# FPGA.net
KiCad netlist of a schematic drawn in Altium Designer
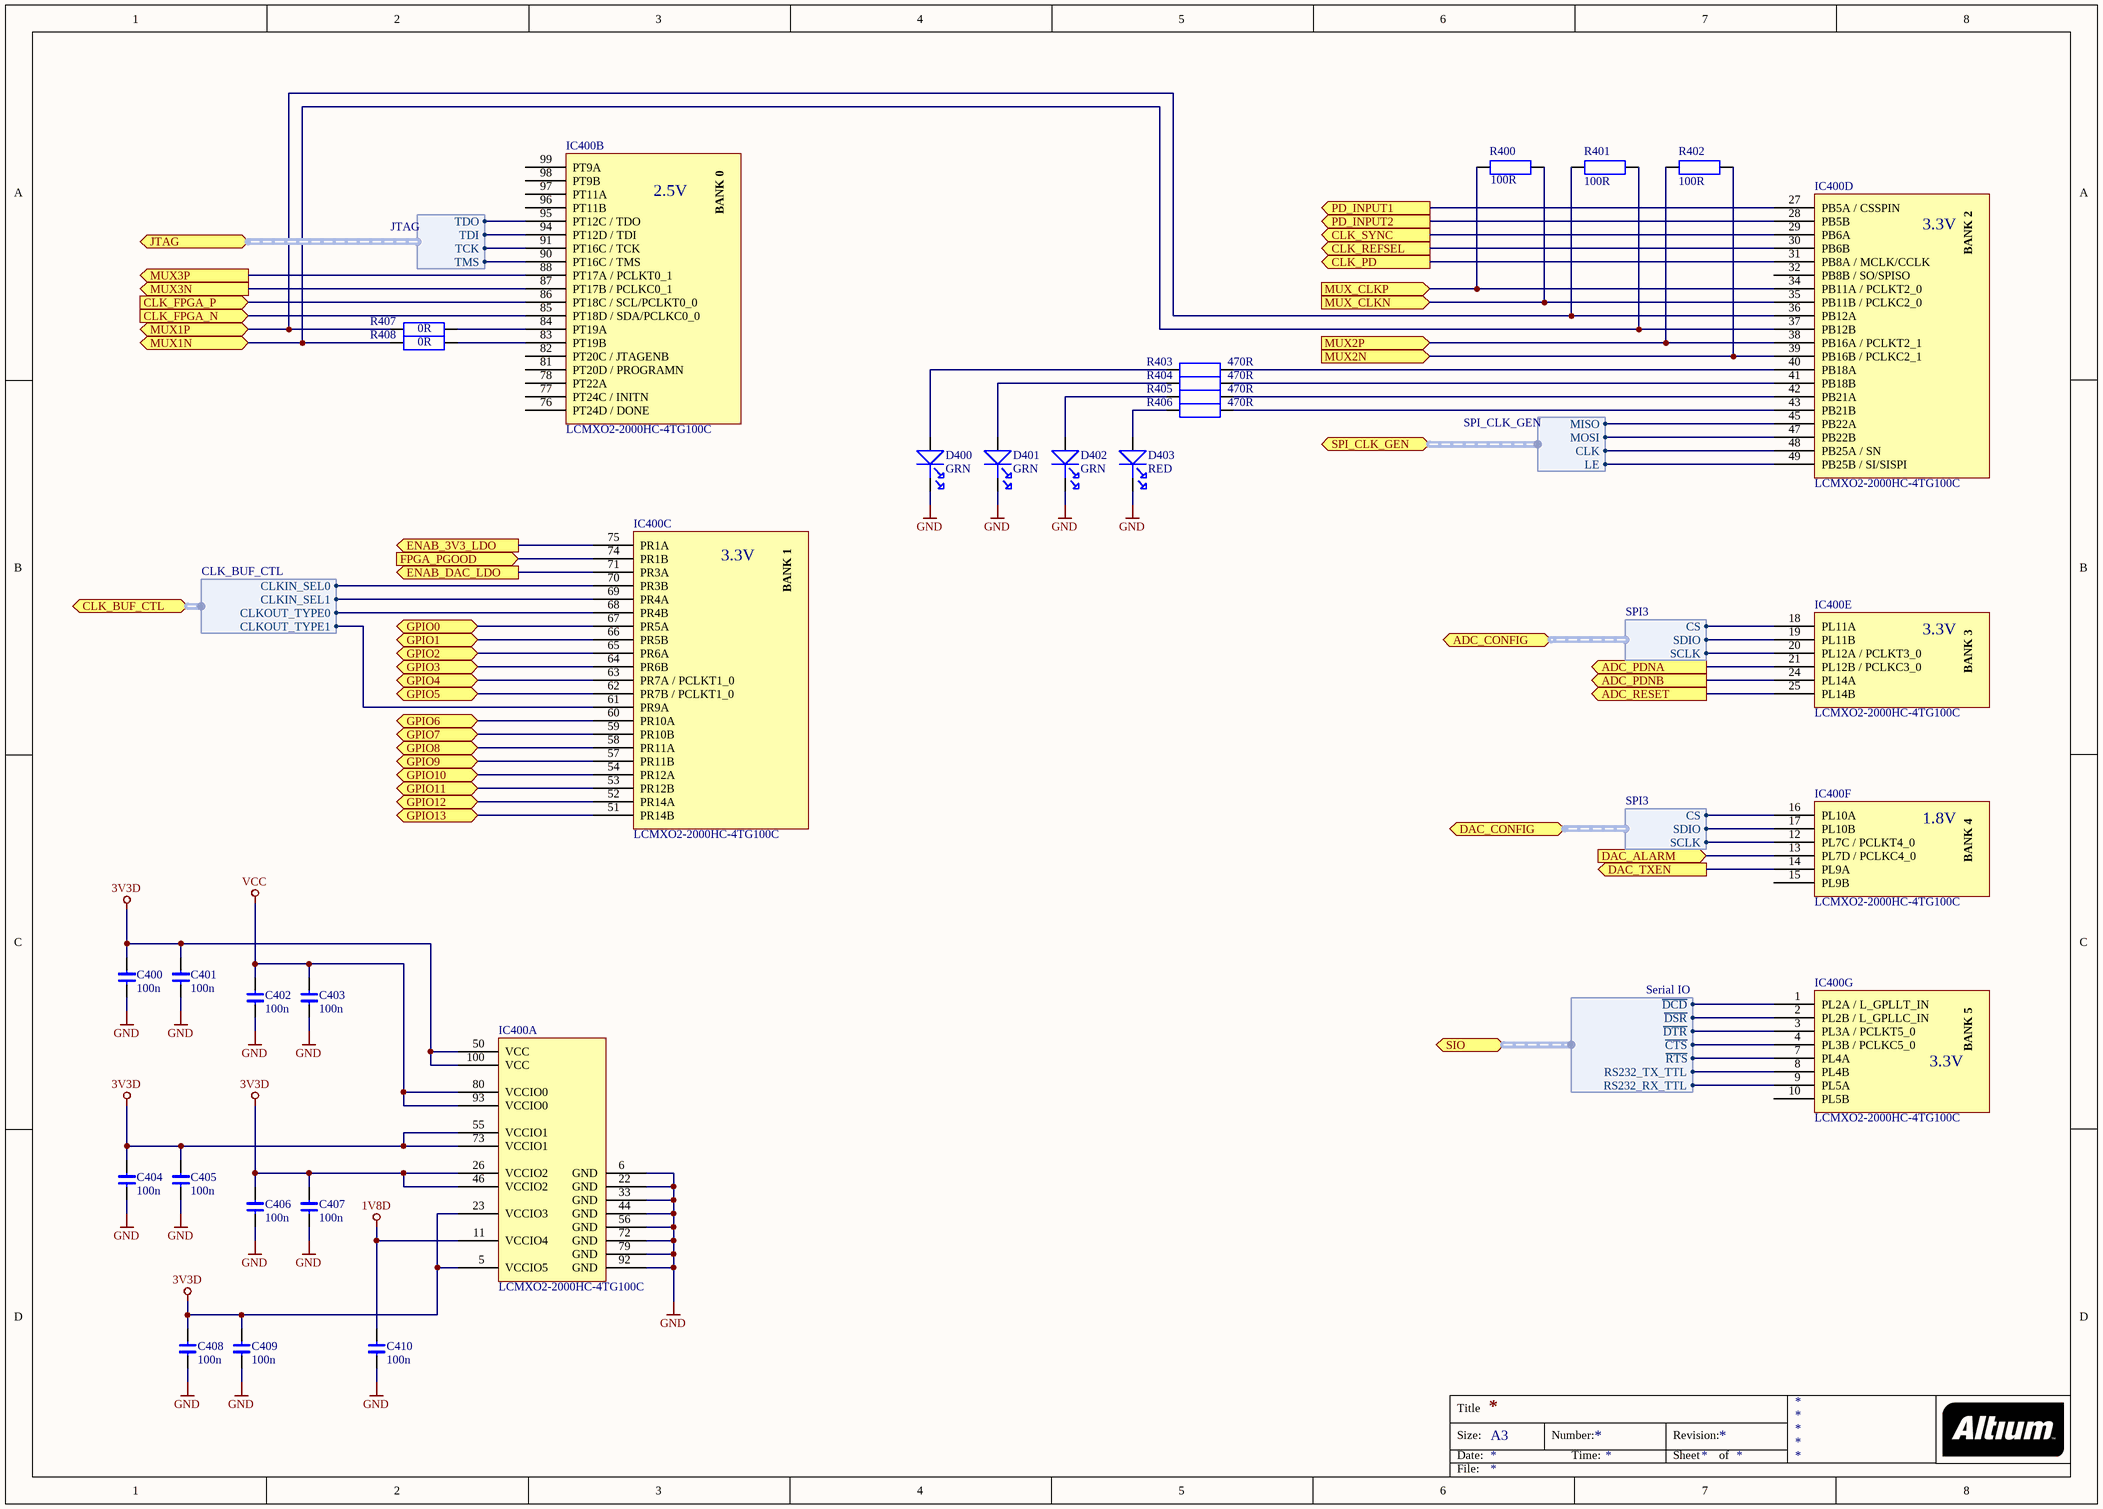
[diagram p0: FPGA.SchDoc]

(export (version "E")
  (design (tool "Eeschema 10.0.6"))
  (components
    (comp (ref "C400")
      (value "100n")
      (footprint "0603 SMALL OUTLINE")
      (description "C")
      (libsource (lib "RCL") (part "C"))
    )
    (comp (ref "C401")
      (value "100n")
      (footprint "0603 SMALL OUTLINE")
      (description "C")
      (libsource (lib "RCL") (part "C"))
    )
    (comp (ref "C402")
      (value "100n")
      (footprint "0603 SMALL OUTLINE")
      (description "C")
      (libsource (lib "RCL") (part "C"))
    )
    (comp (ref "C403")
      (value "100n")
      (footprint "0603 SMALL OUTLINE")
      (description "C")
      (libsource (lib "RCL") (part "C"))
    )
    (comp (ref "C404")
      (value "100n")
      (footprint "0603 SMALL OUTLINE")
      (description "C")
      (libsource (lib "RCL") (part "C"))
    )
    (comp (ref "C405")
      (value "100n")
      (footprint "0603 SMALL OUTLINE")
      (description "C")
      (libsource (lib "RCL") (part "C"))
    )
    (comp (ref "C406")
      (value "100n")
      (footprint "0603 SMALL OUTLINE")
      (description "C")
      (libsource (lib "RCL") (part "C"))
    )
    (comp (ref "C407")
      (value "100n")
      (footprint "0603 SMALL OUTLINE")
      (description "C")
      (libsource (lib "RCL") (part "C"))
    )
    (comp (ref "C408")
      (value "100n")
      (footprint "0603 SMALL OUTLINE")
      (description "C")
      (libsource (lib "RCL") (part "C"))
    )
    (comp (ref "C409")
      (value "100n")
      (footprint "0603 SMALL OUTLINE")
      (description "C")
      (libsource (lib "RCL") (part "C"))
    )
    (comp (ref "C410")
      (value "100n")
      (footprint "0603 SMALL OUTLINE")
      (description "C")
      (libsource (lib "RCL") (part "C"))
    )
    (comp (ref "D400")
      (value "GRN")
      (footprint "LED SMD 0603")
      (description "WURTH 150060VS75000")
      (libsource (lib "OPTO1") (part "LED SMD"))
    )
    (comp (ref "D401")
      (value "GRN")
      (footprint "LED SMD 0603")
      (description "WURTH 150060VS75000")
      (libsource (lib "OPTO1") (part "LED SMD"))
    )
    (comp (ref "D402")
      (value "GRN")
      (footprint "LED SMD 0603")
      (description "WURTH 150060VS75000")
      (libsource (lib "OPTO1") (part "LED SMD"))
    )
    (comp (ref "D403")
      (value "RED")
      (footprint "LED SMD 0603")
      (description "WURTH 150060SS75000")
      (libsource (lib "OPTO1") (part "LED SMD"))
    )
    (comp (ref "IC400")
      (value "LCMXO2-2000HC-4TG100C")
      (footprint "TQFP100")
      (description "Lattice MachXO2")
      (libsource (lib "Private") (part "LCMXO2-2000HC-4TG100C"))
    )
    (comp (ref "R400") (value "100R") (footprint "0402") (description "R") (libsource (lib "RCL") (part "R")))
    (comp (ref "R401") (value "100R") (footprint "0402") (description "R") (libsource (lib "RCL") (part "R")))
    (comp (ref "R402") (value "100R") (footprint "0402") (description "R") (libsource (lib "RCL") (part "R")))
    (comp (ref "R403")
      (value "470R")
      (footprint "0603 SMALL OUTLINE")
      (description "R")
      (libsource (lib "RCL") (part "R"))
    )
    (comp (ref "R404")
      (value "470R")
      (footprint "0603 SMALL OUTLINE")
      (description "R")
      (libsource (lib "RCL") (part "R"))
    )
    (comp (ref "R405")
      (value "470R")
      (footprint "0603 SMALL OUTLINE")
      (description "R")
      (libsource (lib "RCL") (part "R"))
    )
    (comp (ref "R406")
      (value "470R")
      (footprint "0603 SMALL OUTLINE")
      (description "R")
      (libsource (lib "RCL") (part "R"))
    )
    (comp (ref "R407") (value "0R") (footprint "0402") (description "R") (libsource (lib "RCL") (part "R")))
    (comp (ref "R408") (value "0R") (footprint "0402") (description "R") (libsource (lib "RCL") (part "R")))
  )
  (nets
    (net (code "7") (name "/ADC_PDNA") (class "Default")
      (node (ref "IC400") (pin "21") (pinfunction "PL12B_/_PCLKC3_0_21") (pintype "passive"))
    )
    (net (code "8") (name "/ADC_PDNB") (class "Default")
      (node (ref "IC400") (pin "24") (pinfunction "PL14A_24") (pintype "passive"))
    )
    (net (code "9") (name "/ADC_RESET") (class "Default")
      (node (ref "IC400") (pin "25") (pinfunction "PL14B_25") (pintype "passive"))
    )
    (net (code "10") (name "/CLK") (class "Default")
      (node (ref "IC400") (pin "48") (pinfunction "PB25A_/_SN_48") (pintype "passive"))
    )
    (net (code "11") (name "/CLKIN_SEL0") (class "Default")
      (node (ref "IC400") (pin "70") (pinfunction "PR3B_70") (pintype "passive"))
    )
    (net (code "12") (name "/CLKIN_SEL1") (class "Default")
      (node (ref "IC400") (pin "69") (pinfunction "PR4A_69") (pintype "passive"))
    )
    (net (code "13") (name "/CLKOUT_TYPE0") (class "Default")
      (node (ref "IC400") (pin "68") (pinfunction "PR4B_68") (pintype "passive"))
    )
    (net (code "14") (name "/CLKOUT_TYPE1") (class "Default")
      (node (ref "IC400") (pin "61") (pinfunction "PR9A_61") (pintype "passive"))
    )
    (net (code "15") (name "/CLK_FPGA_N") (class "Default")
      (node (ref "IC400") (pin "85") (pinfunction "PT18D_/_SDA/PCLKC0_0_85") (pintype "passive"))
    )
    (net (code "16") (name "/CLK_FPGA_P") (class "Default")
      (node (ref "IC400") (pin "86") (pinfunction "PT18C_/_SCL/PCLKT0_0_86") (pintype "passive"))
    )
    (net (code "17") (name "/CLK_PD") (class "Default")
      (node (ref "IC400") (pin "31") (pinfunction "PB8A_/_MCLK/CCLK_31") (pintype "passive"))
    )
    (net (code "18") (name "/CLK_REFSEL") (class "Default")
      (node (ref "IC400") (pin "30") (pinfunction "PB6B_30") (pintype "passive"))
    )
    (net (code "19") (name "/CLK_SYNC") (class "Default")
      (node (ref "IC400") (pin "29") (pinfunction "PB6A_29") (pintype "passive"))
    )
    (net (code "20") (name "/DAC_ALARM") (class "Default")
      (node (ref "IC400") (pin "13") (pinfunction "PL7D_/_PCLKC4_0_13") (pintype "passive"))
    )
    (net (code "21") (name "/DAC_TXEN") (class "Default")
      (node (ref "IC400") (pin "14") (pinfunction "PL9A_14") (pintype "passive"))
    )
    (net (code "22") (name "/ENAB_3V3_LDO") (class "Default")
      (node (ref "IC400") (pin "75") (pinfunction "PR1A_75") (pintype "passive"))
    )
    (net (code "23") (name "/ENAB_DAC_LDO") (class "Default")
      (node (ref "IC400") (pin "71") (pinfunction "PR3A_71") (pintype "passive"))
    )
    (net (code "24") (name "/FPGA_PGOOD") (class "Default")
      (node (ref "IC400") (pin "74") (pinfunction "PR1B_74") (pintype "passive"))
    )
    (net (code "25") (name "/GPIO0") (class "Default")
      (node (ref "IC400") (pin "67") (pinfunction "PR5A_67") (pintype "passive"))
    )
    (net (code "26") (name "/GPIO1") (class "Default")
      (node (ref "IC400") (pin "66") (pinfunction "PR5B_66") (pintype "passive"))
    )
    (net (code "27") (name "/GPIO2") (class "Default")
      (node (ref "IC400") (pin "65") (pinfunction "PR6A_65") (pintype "passive"))
    )
    (net (code "28") (name "/GPIO3") (class "Default")
      (node (ref "IC400") (pin "64") (pinfunction "PR6B_64") (pintype "passive"))
    )
    (net (code "29") (name "/GPIO4") (class "Default")
      (node (ref "IC400") (pin "63") (pinfunction "PR7A_/_PCLKT1_0_63") (pintype "passive"))
    )
    (net (code "30") (name "/GPIO5") (class "Default")
      (node (ref "IC400") (pin "62") (pinfunction "PR7B_/_PCLKT1_0_62") (pintype "passive"))
    )
    (net (code "31") (name "/GPIO6") (class "Default")
      (node (ref "IC400") (pin "60") (pinfunction "PR10A_60") (pintype "passive"))
    )
    (net (code "32") (name "/GPIO7") (class "Default")
      (node (ref "IC400") (pin "59") (pinfunction "PR10B_59") (pintype "passive"))
    )
    (net (code "33") (name "/GPIO8") (class "Default")
      (node (ref "IC400") (pin "58") (pinfunction "PR11A_58") (pintype "passive"))
    )
    (net (code "34") (name "/GPIO9") (class "Default")
      (node (ref "IC400") (pin "57") (pinfunction "PR11B_57") (pintype "passive"))
    )
    (net (code "35") (name "/GPIO10") (class "Default")
      (node (ref "IC400") (pin "54") (pinfunction "PR12A_54") (pintype "passive"))
    )
    (net (code "36") (name "/GPIO11") (class "Default")
      (node (ref "IC400") (pin "53") (pinfunction "PR12B_53") (pintype "passive"))
    )
    (net (code "37") (name "/GPIO12") (class "Default")
      (node (ref "IC400") (pin "52") (pinfunction "PR14A_52") (pintype "passive"))
    )
    (net (code "38") (name "/GPIO13") (class "Default")
      (node (ref "IC400") (pin "51") (pinfunction "PR14B_51") (pintype "passive"))
    )
    (net (code "39") (name "/LE") (class "Default")
      (node (ref "IC400") (pin "49") (pinfunction "PB25B_/_SI/SISPI_49") (pintype "passive"))
    )
    (net (code "40") (name "/MISO") (class "Default")
      (node (ref "IC400") (pin "45") (pinfunction "PB22A_45") (pintype "passive"))
    )
    (net (code "41") (name "/MOSI") (class "Default")
      (node (ref "IC400") (pin "47") (pinfunction "PB22B_47") (pintype "passive"))
    )
    (net (code "42") (name "/MUX1N") (class "Default")
      (node (ref "IC400") (pin "37") (pinfunction "PB12B_37") (pintype "passive"))
      (node (ref "R401") (pin "1") (pinfunction "1_1") (pintype "passive"))
      (node (ref "R408") (pin "2") (pinfunction "2_2") (pintype "passive"))
    )
    (net (code "43") (name "/MUX1P") (class "Default")
      (node (ref "IC400") (pin "36") (pinfunction "PB12A_36") (pintype "passive"))
      (node (ref "R401") (pin "2") (pinfunction "2_2") (pintype "passive"))
      (node (ref "R407") (pin "2") (pinfunction "2_2") (pintype "passive"))
    )
    (net (code "44") (name "/MUX2N") (class "Default")
      (node (ref "IC400") (pin "39") (pinfunction "PB16B_/_PCLKC2_1_39") (pintype "passive"))
      (node (ref "R402") (pin "1") (pinfunction "1_1") (pintype "passive"))
    )
    (net (code "45") (name "/MUX2P") (class "Default")
      (node (ref "IC400") (pin "38") (pinfunction "PB16A_/_PCLKT2_1_38") (pintype "passive"))
      (node (ref "R402") (pin "2") (pinfunction "2_2") (pintype "passive"))
    )
    (net (code "46") (name "/MUX3N") (class "Default")
      (node (ref "IC400") (pin "87") (pinfunction "PT17B_/_PCLKC0_1_87") (pintype "passive"))
    )
    (net (code "47") (name "/MUX3P") (class "Default")
      (node (ref "IC400") (pin "88") (pinfunction "PT17A_/_PCLKT0_1_88") (pintype "passive"))
    )
    (net (code "48") (name "/MUX_CLKN") (class "Default")
      (node (ref "IC400") (pin "35") (pinfunction "PB11B_/_PCLKC2_0_35") (pintype "passive"))
      (node (ref "R400") (pin "1") (pinfunction "1_1") (pintype "passive"))
    )
    (net (code "49") (name "/MUX_CLKP") (class "Default")
      (node (ref "IC400") (pin "34") (pinfunction "PB11A_/_PCLKT2_0_34") (pintype "passive"))
      (node (ref "R400") (pin "2") (pinfunction "2_2") (pintype "passive"))
    )
    (net (code "50") (name "/PD_INPUT1") (class "Default")
      (node (ref "IC400") (pin "27") (pinfunction "PB5A_/_CSSPIN_27") (pintype "passive"))
    )
    (net (code "51") (name "/PD_INPUT2") (class "Default")
      (node (ref "IC400") (pin "28") (pinfunction "PB5B_28") (pintype "passive"))
    )
    (net (code "52") (name "/RS232_RX_TTL") (class "Default")
      (node (ref "IC400") (pin "9") (pinfunction "PL5A_9") (pintype "passive"))
    )
    (net (code "53") (name "/RS232_TX_TTL") (class "Default")
      (node (ref "IC400") (pin "8") (pinfunction "PL4B_8") (pintype "passive"))
    )
    (net (code "54") (name "/TCK") (class "Default")
      (node (ref "IC400") (pin "91") (pinfunction "PT16C_/_TCK_91") (pintype "passive"))
    )
    (net (code "55") (name "/TDI") (class "Default")
      (node (ref "IC400") (pin "94") (pinfunction "PT12D_/_TDI_94") (pintype "passive"))
    )
    (net (code "56") (name "/TDO") (class "Default")
      (node (ref "IC400") (pin "95") (pinfunction "PT12C_/_TDO_95") (pintype "passive"))
    )
    (net (code "57") (name "/TMS") (class "Default")
      (node (ref "IC400") (pin "90") (pinfunction "PT16C_/_TMS_90") (pintype "passive"))
    )
    (net (code "63") (name "/~{CTS}") (class "Default")
      (node (ref "IC400") (pin "4") (pinfunction "PL3B_/_PCLKC5_0_4") (pintype "passive"))
    )
    (net (code "64") (name "/~{DCD}") (class "Default")
      (node (ref "IC400") (pin "1") (pinfunction "PL2A_/_L_GPLLT_IN_1") (pintype "passive"))
    )
    (net (code "65") (name "/~{DSR}") (class "Default")
      (node (ref "IC400") (pin "2") (pinfunction "PL2B_/_L_GPLLC_IN_2") (pintype "passive"))
    )
    (net (code "66") (name "/~{DTR}") (class "Default")
      (node (ref "IC400") (pin "3") (pinfunction "PL3A_/_PCLKT5_0_3") (pintype "passive"))
    )
    (net (code "67") (name "/~{RTS}") (class "Default")
      (node (ref "IC400") (pin "7") (pinfunction "PL4A_7") (pintype "passive"))
    )
    (net (code "68") (name "1V8D") (class "Default")
      (node (ref "C410") (pin "1") (pinfunction "1_1") (pintype "passive"))
      (node (ref "IC400") (pin "11") (pinfunction "VCCIO4_11") (pintype "passive"))
    )
    (net (code "69") (name "3V3D") (class "Default")
      (node (ref "C400") (pin "1") (pinfunction "1_1") (pintype "passive"))
      (node (ref "C401") (pin "1") (pinfunction "1_1") (pintype "passive"))
      (node (ref "C404") (pin "1") (pinfunction "1_1") (pintype "passive"))
      (node (ref "C405") (pin "1") (pinfunction "1_1") (pintype "passive"))
      (node (ref "C406") (pin "1") (pinfunction "1_1") (pintype "passive"))
      (node (ref "C407") (pin "1") (pinfunction "1_1") (pintype "passive"))
      (node (ref "C408") (pin "1") (pinfunction "1_1") (pintype "passive"))
      (node (ref "C409") (pin "1") (pinfunction "1_1") (pintype "passive"))
      (node (ref "IC400") (pin "100") (pinfunction "VCC_100") (pintype "passive"))
      (node (ref "IC400") (pin "23") (pinfunction "VCCIO3_23") (pintype "passive"))
      (node (ref "IC400") (pin "26") (pinfunction "VCCIO2_26") (pintype "passive"))
      (node (ref "IC400") (pin "46") (pinfunction "VCCIO2_46") (pintype "passive"))
      (node (ref "IC400") (pin "5") (pinfunction "VCCIO5_5") (pintype "passive"))
      (node (ref "IC400") (pin "50") (pinfunction "VCC_50") (pintype "passive"))
      (node (ref "IC400") (pin "55") (pinfunction "VCCIO1_55") (pintype "passive"))
      (node (ref "IC400") (pin "73") (pinfunction "VCCIO1_73") (pintype "passive"))
    )
    (net (code "70") (name "GND") (class "Default")
      (node (ref "C400") (pin "2") (pinfunction "2_2") (pintype "passive"))
      (node (ref "C401") (pin "2") (pinfunction "2_2") (pintype "passive"))
      (node (ref "C402") (pin "2") (pinfunction "2_2") (pintype "passive"))
      (node (ref "C403") (pin "2") (pinfunction "2_2") (pintype "passive"))
      (node (ref "C404") (pin "2") (pinfunction "2_2") (pintype "passive"))
      (node (ref "C405") (pin "2") (pinfunction "2_2") (pintype "passive"))
      (node (ref "C406") (pin "2") (pinfunction "2_2") (pintype "passive"))
      (node (ref "C407") (pin "2") (pinfunction "2_2") (pintype "passive"))
      (node (ref "C408") (pin "2") (pinfunction "2_2") (pintype "passive"))
      (node (ref "C409") (pin "2") (pinfunction "2_2") (pintype "passive"))
      (node (ref "C410") (pin "2") (pinfunction "2_2") (pintype "passive"))
      (node (ref "D400") (pin "K") (pinfunction "K_K") (pintype "passive"))
      (node (ref "D401") (pin "K") (pinfunction "K_K") (pintype "passive"))
      (node (ref "D402") (pin "K") (pinfunction "K_K") (pintype "passive"))
      (node (ref "D403") (pin "K") (pinfunction "K_K") (pintype "passive"))
      (node (ref "IC400") (pin "22") (pinfunction "GND_22") (pintype "passive"))
      (node (ref "IC400") (pin "33") (pinfunction "GND_33") (pintype "passive"))
      (node (ref "IC400") (pin "44") (pinfunction "GND_44") (pintype "passive"))
      (node (ref "IC400") (pin "56") (pinfunction "GND_56") (pintype "passive"))
      (node (ref "IC400") (pin "6") (pinfunction "GND_6") (pintype "passive"))
      (node (ref "IC400") (pin "72") (pinfunction "GND_72") (pintype "passive"))
      (node (ref "IC400") (pin "79") (pinfunction "GND_79") (pintype "passive"))
      (node (ref "IC400") (pin "92") (pinfunction "GND_92") (pintype "passive"))
    )
    (net (code "71") (name "Net-(D400-PadA)") (class "Default")
      (node (ref "D400") (pin "A") (pinfunction "A_A") (pintype "passive"))
      (node (ref "R403") (pin "2") (pinfunction "2_2") (pintype "passive"))
    )
    (net (code "72") (name "Net-(D401-PadA)") (class "Default")
      (node (ref "D401") (pin "A") (pinfunction "A_A") (pintype "passive"))
      (node (ref "R404") (pin "2") (pinfunction "2_2") (pintype "passive"))
    )
    (net (code "73") (name "Net-(D402-PadA)") (class "Default")
      (node (ref "D402") (pin "A") (pinfunction "A_A") (pintype "passive"))
      (node (ref "R405") (pin "2") (pinfunction "2_2") (pintype "passive"))
    )
    (net (code "74") (name "Net-(D403-PadA)") (class "Default")
      (node (ref "D403") (pin "A") (pinfunction "A_A") (pintype "passive"))
      (node (ref "R406") (pin "2") (pinfunction "2_2") (pintype "passive"))
    )
    (net (code "75") (name "Net-(IC400B-PT19A)") (class "Default")
      (node (ref "IC400") (pin "84") (pinfunction "PT19A_84") (pintype "passive"))
      (node (ref "R407") (pin "1") (pinfunction "1_1") (pintype "passive"))
    )
    (net (code "76") (name "Net-(IC400B-PT19B)") (class "Default")
      (node (ref "IC400") (pin "83") (pinfunction "PT19B_83") (pintype "passive"))
      (node (ref "R408") (pin "1") (pinfunction "1_1") (pintype "passive"))
    )
    (net (code "77") (name "Net-(IC400D-PB18A)") (class "Default")
      (node (ref "IC400") (pin "40") (pinfunction "PB18A_40") (pintype "passive"))
      (node (ref "R403") (pin "1") (pinfunction "1_1") (pintype "passive"))
    )
    (net (code "78") (name "Net-(IC400D-PB18B)") (class "Default")
      (node (ref "IC400") (pin "41") (pinfunction "PB18B_41") (pintype "passive"))
      (node (ref "R404") (pin "1") (pinfunction "1_1") (pintype "passive"))
    )
    (net (code "79") (name "Net-(IC400D-PB21A)") (class "Default")
      (node (ref "IC400") (pin "42") (pinfunction "PB21A_42") (pintype "passive"))
      (node (ref "R405") (pin "1") (pinfunction "1_1") (pintype "passive"))
    )
    (net (code "80") (name "Net-(IC400D-PB21B)") (class "Default")
      (node (ref "IC400") (pin "43") (pinfunction "PB21B_43") (pintype "passive"))
      (node (ref "R406") (pin "1") (pinfunction "1_1") (pintype "passive"))
    )
    (net (code "81") (name "VCC") (class "Default")
      (node (ref "C402") (pin "1") (pinfunction "1_1") (pintype "passive"))
      (node (ref "C403") (pin "1") (pinfunction "1_1") (pintype "passive"))
      (node (ref "IC400") (pin "80") (pinfunction "VCCIO0_80") (pintype "passive"))
      (node (ref "IC400") (pin "93") (pinfunction "VCCIO0_93") (pintype "passive"))
    )
    (net (code "82") (name "unconnected-(IC400B-PT9A-Pad99)") (class "Default")
      (node (ref "IC400") (pin "99") (pinfunction "PT9A_99") (pintype "passive"))
    )
    (net (code "83") (name "unconnected-(IC400B-PT9B-Pad98)") (class "Default")
      (node (ref "IC400") (pin "98") (pinfunction "PT9B_98") (pintype "passive"))
    )
    (net (code "84") (name "unconnected-(IC400B-PT11A-Pad97)") (class "Default")
      (node (ref "IC400") (pin "97") (pinfunction "PT11A_97") (pintype "passive"))
    )
    (net (code "85") (name "unconnected-(IC400B-PT11B-Pad96)") (class "Default")
      (node (ref "IC400") (pin "96") (pinfunction "PT11B_96") (pintype "passive"))
    )
    (net (code "86") (name "unconnected-(IC400B-PT20C_{slash}_JTAGENB-Pad82)") (class "Default")
      (node (ref "IC400") (pin "82") (pinfunction "PT20C_/_JTAGENB_82") (pintype "passive"))
    )
    (net (code "87") (name "unconnected-(IC400B-PT20D_{slash}_PROGRAMN-Pad81)") (class "Default")
      (node (ref "IC400") (pin "81") (pinfunction "PT20D_/_PROGRAMN_81") (pintype "passive"))
    )
    (net (code "88") (name "unconnected-(IC400B-PT22A-Pad78)") (class "Default")
      (node (ref "IC400") (pin "78") (pinfunction "PT22A_78") (pintype "passive"))
    )
    (net (code "89") (name "unconnected-(IC400B-PT24C_{slash}_INITN-Pad77)") (class "Default")
      (node (ref "IC400") (pin "77") (pinfunction "PT24C_/_INITN_77") (pintype "passive"))
    )
    (net (code "90") (name "unconnected-(IC400B-PT24D_{slash}_DONE-Pad76)") (class "Default")
      (node (ref "IC400") (pin "76") (pinfunction "PT24D_/_DONE_76") (pintype "passive"))
    )
    (net (code "91") (name "unconnected-(IC400D-PB8B_{slash}_SO{slash}SPISO-Pad32)") (class "Default")
      (node (ref "IC400") (pin "32") (pinfunction "PB8B_/_SO/SPISO_32") (pintype "passive"))
    )
    (net (code "92") (name "unconnected-(IC400E-PL11A-Pad18)") (class "Default")
      (node (ref "IC400") (pin "18") (pinfunction "PL11A_18") (pintype "passive"))
    )
    (net (code "93") (name "unconnected-(IC400E-PL11B-Pad19)") (class "Default")
      (node (ref "IC400") (pin "19") (pinfunction "PL11B_19") (pintype "passive"))
    )
    (net (code "94") (name "unconnected-(IC400E-PL12A_{slash}_PCLKT3_0-Pad20)") (class "Default")
      (node (ref "IC400") (pin "20") (pinfunction "PL12A_/_PCLKT3_0_20") (pintype "passive"))
    )
    (net (code "95") (name "unconnected-(IC400F-PL7C_{slash}_PCLKT4_0-Pad12)") (class "Default")
      (node (ref "IC400") (pin "12") (pinfunction "PL7C_/_PCLKT4_0_12") (pintype "passive"))
    )
    (net (code "96") (name "unconnected-(IC400F-PL9B-Pad15)") (class "Default")
      (node (ref "IC400") (pin "15") (pinfunction "PL9B_15") (pintype "passive"))
    )
    (net (code "97") (name "unconnected-(IC400F-PL10A-Pad16)") (class "Default")
      (node (ref "IC400") (pin "16") (pinfunction "PL10A_16") (pintype "passive"))
    )
    (net (code "98") (name "unconnected-(IC400F-PL10B-Pad17)") (class "Default")
      (node (ref "IC400") (pin "17") (pinfunction "PL10B_17") (pintype "passive"))
    )
    (net (code "99") (name "unconnected-(IC400G-PL5B-Pad10)") (class "Default")
      (node (ref "IC400") (pin "10") (pinfunction "PL5B_10") (pintype "passive"))
    )
  )
)
